# L3G4200.net
KiCad netlist of a schematic drawn in Altium Designer
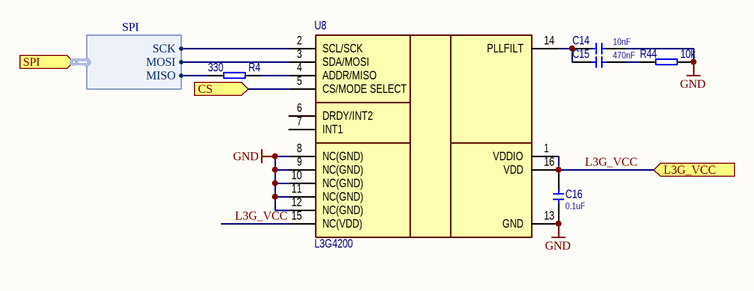
[diagram p0: L3G4200.SchDoc]

(export (version "E")
  (design (tool "Eeschema 10.0.6"))
  (components
    (comp (ref "C14")
      (value "10nF")
      (footprint "CERCAP 0402")
      (description "Capacitor")
      (fields (field (name "Comment") "CERCAP 0402 10nF * X7R"))
      (libsource (lib "!main") (part "!Capacitor"))
    )
    (comp (ref "C15")
      (value "470nF")
      (footprint "CERCAP 0402")
      (description "Capacitor")
      (fields (field (name "Comment") "CERCAP 0402 470nF * X7R"))
      (libsource (lib "!main") (part "!Capacitor"))
    )
    (comp (ref "C16")
      (value "0.1uF")
      (footprint "CERCAP 0402")
      (description "Capacitor")
      (fields (field (name "Comment") "CERCAP 0402 0.1uF * X7R"))
      (libsource (lib "!main") (part "!Capacitor"))
    )
    (comp (ref "R4")
      (value "330")
      (footprint "RES 0402")
      (description "Resistor")
      (fields (field (name "Comment") "RES 0402 330"))
      (libsource (lib "!main") (part "!Resistor"))
    )
    (comp (ref "R44")
      (value "10k")
      (footprint "RES 0402")
      (description "Resistor")
      (fields (field (name "Comment") "RES 0402 10k"))
      (libsource (lib "!main") (part "!Resistor"))
    )
    (comp (ref "U8")
      (value "L3G4200")
      (footprint "LGA16_L3G4200")
      (libsource (lib "sensors") (part "L3G4200"))
    )
  )
  (nets
    (net (code "2") (name "/CS") (class "Default")
      (node (ref "U8") (pin "5") (pinfunction "CS/MODE_SELECT_5") (pintype "passive"))
    )
    (net (code "3") (name "/L3G_VCC") (class "Default")
      (node (ref "C16") (pin "2") (pintype "passive"))
      (node (ref "U8") (pin "1") (pinfunction "VDDIO_1") (pintype "passive"))
      (node (ref "U8") (pin "15") (pinfunction "NC(VDD)_15") (pintype "passive"))
      (node (ref "U8") (pin "16") (pinfunction "VDD_16") (pintype "passive"))
    )
    (net (code "4") (name "/MISO") (class "Default")
      (node (ref "R4") (pin "1") (pinfunction "11_1") (pintype "passive"))
    )
    (net (code "5") (name "/MOSI") (class "Default")
      (node (ref "U8") (pin "3") (pinfunction "SDA/MOSI_3") (pintype "passive"))
    )
    (net (code "6") (name "/SCK") (class "Default")
      (node (ref "U8") (pin "2") (pinfunction "SCL/SCK_2") (pintype "passive"))
    )
    (net (code "8") (name "GND") (class "Default")
      (node (ref "C14") (pin "2") (pintype "passive"))
      (node (ref "C16") (pin "1") (pintype "passive"))
      (node (ref "R44") (pin "2") (pinfunction "12_2") (pintype "passive"))
      (node (ref "U8") (pin "10") (pinfunction "NC(GND)_10") (pintype "passive"))
      (node (ref "U8") (pin "11") (pinfunction "NC(GND)_11") (pintype "passive"))
      (node (ref "U8") (pin "12") (pinfunction "NC(GND)_12") (pintype "passive"))
      (node (ref "U8") (pin "13") (pinfunction "GND_13") (pintype "passive"))
      (node (ref "U8") (pin "8") (pinfunction "NC(GND)_8") (pintype "passive"))
      (node (ref "U8") (pin "9") (pinfunction "NC(GND)_9") (pintype "passive"))
    )
    (net (code "9") (name "Net-(R4-12)") (class "Default")
      (node (ref "R4") (pin "2") (pinfunction "12_2") (pintype "passive"))
      (node (ref "U8") (pin "4") (pinfunction "ADDR/MISO_4") (pintype "passive"))
    )
    (net (code "10") (name "Net-(R44-11)") (class "Default")
      (node (ref "C15") (pin "2") (pintype "passive"))
      (node (ref "R44") (pin "1") (pinfunction "11_1") (pintype "passive"))
    )
    (net (code "11") (name "Net-(U8-PLLFILT)") (class "Default")
      (node (ref "C14") (pin "1") (pintype "passive"))
      (node (ref "C15") (pin "1") (pintype "passive"))
      (node (ref "U8") (pin "14") (pinfunction "PLLFILT_14") (pintype "passive"))
    )
    (net (code "12") (name "unconnected-(U8-DRDY{slash}INT2-Pad6)") (class "Default")
      (node (ref "U8") (pin "6") (pinfunction "DRDY/INT2_6") (pintype "passive"))
    )
    (net (code "13") (name "unconnected-(U8-INT1-Pad7)") (class "Default")
      (node (ref "U8") (pin "7") (pinfunction "INT1_7") (pintype "passive"))
    )
  )
)
